# Led_Matrix_Main.net
KiCad netlist of a schematic drawn in Altium Designer
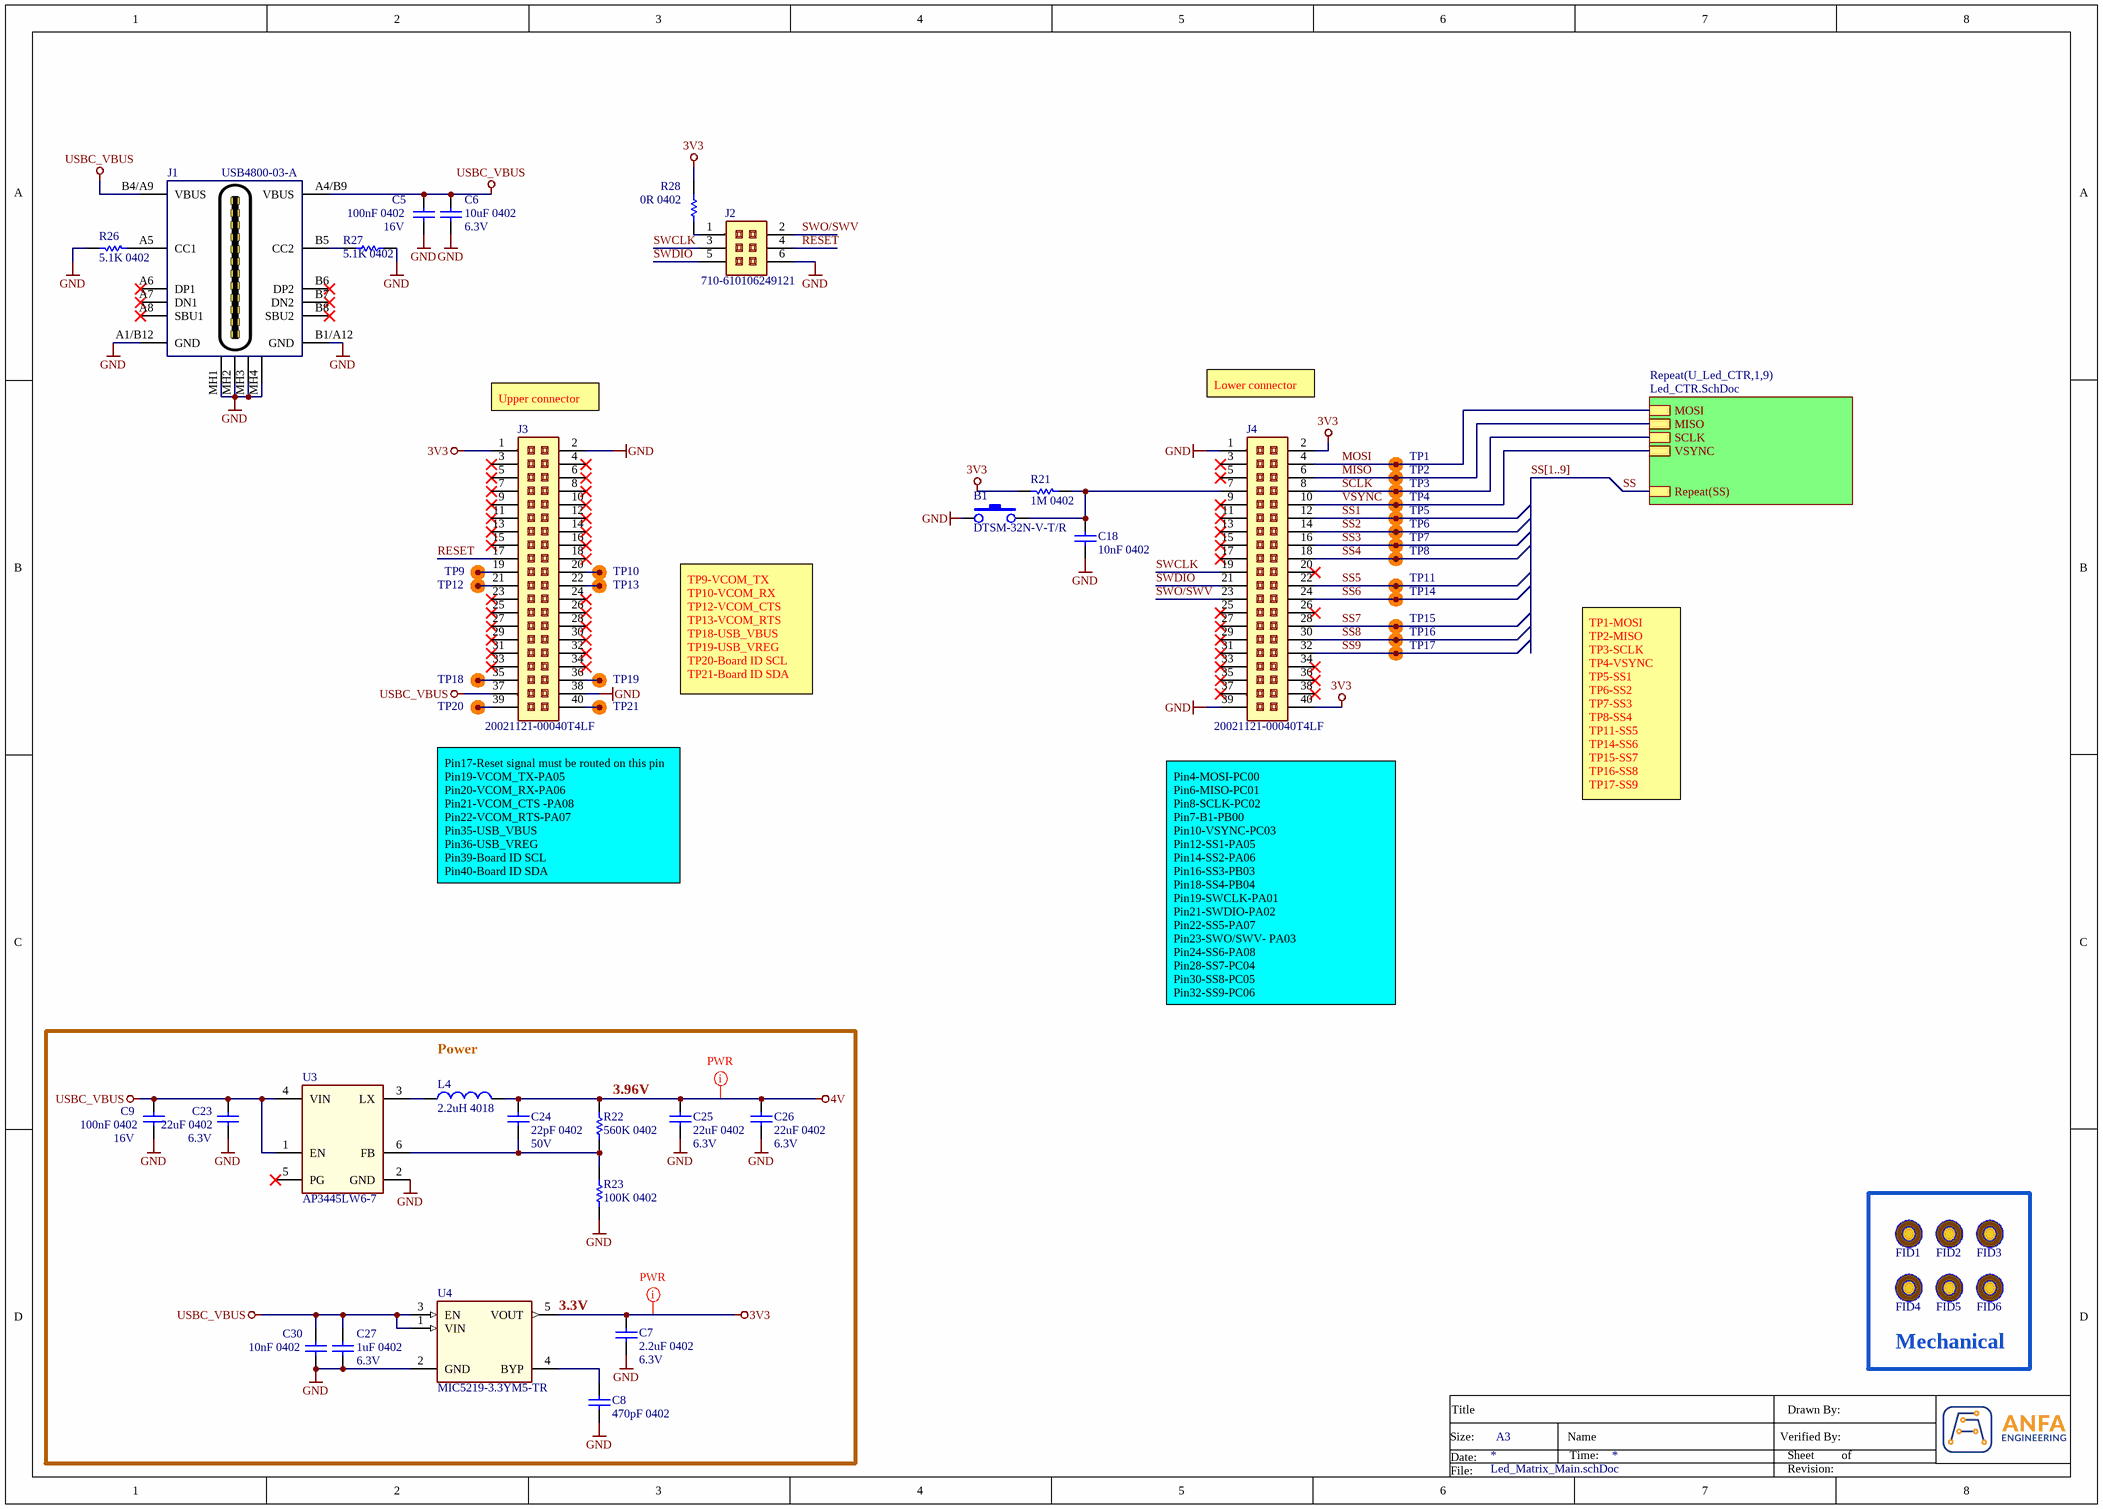
[diagram p0: Led_Matrix_Main.schDoc]

(export (version "E")
  (design (tool "Eeschema 10.0.6"))
  (components
    (comp (ref "B1")
      (value "DTSM-32N-V-T/R")
      (footprint "DTSM-32N-V")
      (description "SWITCH TACTILE SMT 3.5mm * 6mm , brown 160gf")
      (fields (field (name "MANUFACTURER") "Diptronics"))
      (libsource (lib "Led_Matrix") (part "SW-TACTILE_ON/OFF_DTSM-32N-V-T/R"))
    )
    (comp (ref "C5")
      (value "100nF 0402")
      (footprint "CAPC0402(1005)70")
      (description "Surface Mount Ceramic Multilayer Capacitor 100nF, ± 10%, X7R, 16V, 0402")
      (fields
        (field (name "TOLERANCE") "10%")
        (field (name "MANUFACTURER") "Murata")
        (field (name "VOLTAGE") "16V")
      )
      (libsource (lib "Led_Matrix") (part "C_100nF_0402_16V_X7R"))
    )
    (comp (ref "C6")
      (value "10uF 0402")
      (footprint "CAPC0402(1005)70")
      (description "Surface Mount Ceramic Multilayer Capacitor 10uF, ± 20 %, X5R, 6.3V, 0402")
      (fields
        (field (name "TOLERANCE") "20%")
        (field (name "MANUFACTURER") "Murata")
        (field (name "VOLTAGE") "6.3V")
      )
      (libsource (lib "Led_Matrix") (part "C_10uF_0402_6.3V_X5R"))
    )
    (comp (ref "C7")
      (value "2.2uF 0402")
      (footprint "CAPC0402(1005)70")
      (description "Surface Mount Ceramic Multilayer Capacitor 2.2uF, ± 10%, X5R, 6.3V, 0402")
      (fields
        (field (name "MANUFACTURER") "Murata")
        (field (name "MANUFACTURER PART NUMBER") "GRM155R60J225KE01D")
        (field (name "VOLTAGE") "6.3V")
      )
      (libsource (lib "Led_Matrix") (part "C_2.2uF_0402_6.3V_X5R"))
    )
    (comp (ref "C8")
      (value "470pF 0402")
      (footprint "CAPC0402(1005)33")
      (description "Multilayer Ceramic Capacitors MLCC - SMD/SMT 0402 470pF 10V C0G 10%")
      (fields
        (field (name "MANUFACTURER") "Vishay")
        (field (name "MANUFACTURER PART NUMBER") "VJ0402A471KXQPW1BC")
      )
      (libsource (lib "Led_Matrix") (part "C_470pF_0402_10V_C0G"))
    )
    (comp (ref "C9")
      (value "100nF 0402")
      (footprint "CAPC0402(1005)70")
      (description "Surface Mount Ceramic Multilayer Capacitor 100nF, ± 10%, X7R, 16V, 0402")
      (fields
        (field (name "TOLERANCE") "10%")
        (field (name "MANUFACTURER") "Murata")
        (field (name "VOLTAGE") "16V")
      )
      (libsource (lib "Led_Matrix") (part "C_100nF_0402_16V_X7R"))
    )
    (comp (ref "C18")
      (value "10nF 0402")
      (footprint "CAPC0402(1005)33")
      (description "Cap Ceramic 0.01uF 50V X7R 10% SMD 0402 125C Paper T/R")
      (fields (field (name "TOLERANCE") "10%") (field (name "MANUFACTURER") "Vishay Vitramon"))
      (libsource (lib "Led_Matrix") (part "C_10nF_0402_50V_X7R"))
    )
    (comp (ref "C23")
      (value "22uF 0402")
      (footprint "CAPC0402(1005)70")
      (description "Multilayer Ceramic Capacitors MLCC - SMD/SMT 6.3V 22uF X5R 0402 20%")
      (fields
        (field (name "MANUFACTURER") "KYOCERA AVX")
        (field (name "MANUFACTURER PART NUMBER") "04026D226MAT2A")
        (field (name "VOLTAGE") "6.3V")
      )
      (libsource (lib "Led_Matrix") (part "C_22uF_0402_6.3V_X5R"))
    )
    (comp (ref "C24")
      (value "22pF 0402")
      (footprint "CAPC0402(1005)70")
      (description "Surface Mount Ceramic Multilayer Capacitor 22pF, ± 5%, C0G, 50V, 0402")
      (fields
        (field (name "MANUFACTURER") "Kyocera AVX")
        (field (name "MANUFACTURER PART NUMBER") "04025A220JAT2A")
        (field (name "VOLTAGE") "50V")
      )
      (libsource (lib "Led_Matrix") (part "C_22pF_0402_50V_C0G"))
    )
    (comp (ref "C25")
      (value "22uF 0402")
      (footprint "CAPC0402(1005)70")
      (description "Multilayer Ceramic Capacitors MLCC - SMD/SMT 6.3V 22uF X5R 0402 20%")
      (fields
        (field (name "MANUFACTURER") "KYOCERA AVX")
        (field (name "MANUFACTURER PART NUMBER") "04026D226MAT2A")
        (field (name "VOLTAGE") "6.3V")
      )
      (libsource (lib "Led_Matrix") (part "C_22uF_0402_6.3V_X5R"))
    )
    (comp (ref "C26")
      (value "22uF 0402")
      (footprint "CAPC0402(1005)70")
      (description "Multilayer Ceramic Capacitors MLCC - SMD/SMT 6.3V 22uF X5R 0402 20%")
      (fields
        (field (name "MANUFACTURER") "KYOCERA AVX")
        (field (name "MANUFACTURER PART NUMBER") "04026D226MAT2A")
        (field (name "VOLTAGE") "6.3V")
      )
      (libsource (lib "Led_Matrix") (part "C_22uF_0402_6.3V_X5R"))
    )
    (comp (ref "C27")
      (value "1uF 0402")
      (footprint "CAPC0402(1005)70")
      (description "Surface Mount Ceramic Multilayer Capacitor 1uF, ± 20%, X5R, 6.3V, 0402")
      (fields
        (field (name "TOLERANCE") "20%")
        (field (name "MANUFACTURER") "Murata")
        (field (name "VOLTAGE") "6.3V")
      )
      (libsource (lib "Led_Matrix") (part "C_1uF_0402_6.3V_X5R"))
    )
    (comp (ref "C30")
      (value "10nF 0402")
      (footprint "CAPC0402(1005)33")
      (description "Cap Ceramic 0.01uF 50V X7R 10% SMD 0402 125C Paper T/R")
      (fields
        (field (name "MANUFACTURER") "Vishay Vitramon")
        (field (name "MANUFACTURER PART NUMBER") "VJ0402Y103KXACW1BC")
      )
      (libsource (lib "Led_Matrix") (part "C_10nF_0402_50V_X7R"))
    )
    (comp (ref "FID1")
      (value "~")
      (footprint "FID1")
      (description "Fiducial with various available footprints")
      (libsource (lib "AL_Connectors") (part "MECH_FIDUCIAL"))
    )
    (comp (ref "FID2")
      (value "~")
      (footprint "FID1")
      (description "Fiducial with various available footprints")
      (libsource (lib "AL_Connectors") (part "MECH_FIDUCIAL"))
    )
    (comp (ref "FID3")
      (value "~")
      (footprint "FID1")
      (description "Fiducial with various available footprints")
      (libsource (lib "AL_Connectors") (part "MECH_FIDUCIAL"))
    )
    (comp (ref "FID4")
      (value "~")
      (footprint "FID1")
      (description "Fiducial with various available footprints")
      (libsource (lib "AL_Connectors") (part "MECH_FIDUCIAL"))
    )
    (comp (ref "FID5")
      (value "~")
      (footprint "FID1")
      (description "Fiducial with various available footprints")
      (libsource (lib "AL_Connectors") (part "MECH_FIDUCIAL"))
    )
    (comp (ref "FID6")
      (value "~")
      (footprint "FID1")
      (description "Fiducial with various available footprints")
      (libsource (lib "AL_Connectors") (part "MECH_FIDUCIAL"))
    )
    (comp (ref "J1")
      (value "USB4800-03-A")
      (footprint "USB4800-03-A")
      (description "USB Connectors USB2.0 Type C Rcpt, SMT, Hrz, 3.5mm elevated, 16 Pin")
      (fields (field (name "MANUFACTURER") "GCT"))
      (libsource (lib "Led_Matrix") (part "USB-C_3.0_USB4800-03-A"))
    )
    (comp (ref "J2")
      (value "710-610106249121")
      (footprint "HDR_2X3_2.54mm_MALE")
      (description "Headers & Wire Housings WR-PHD 2.54mm Hdr 6P Dual RA Gold")
      (fields
        (field (name "MANUFACTURER") "Wurth Elektronik")
        (field (name "MANUFACTURER PART NUMBER") "610106249121")
      )
      (libsource (lib "Led_Matrix") (part "HEADER_2X3_RA_MALE_2.54mm_710-610106249121"))
    )
    (comp (ref "J3")
      (value "20021121-00040T4LF")
      (footprint "20021121-00040T4LF")
      (description "Headers & Wire Housings 1.27mm BTB, Hdr, SMT Unshrd, 40 P, Tub")
      (fields (field (name "MANUFACTURER") "Amphenol FCI"))
      (libsource (lib "Led_Matrix") (part "HEADER_2X20_RA_MALE_1,27mm_649-221121-00040T4LF"))
    )
    (comp (ref "J4")
      (value "20021121-00040T4LF")
      (footprint "20021121-00040T4LF")
      (description "Headers & Wire Housings 1.27mm BTB, Hdr, SMT Unshrd, 40 P, Tub")
      (fields (field (name "MANUFACTURER") "Amphenol FCI"))
      (libsource (lib "Led_Matrix") (part "HEADER_2X20_RA_MALE_1,27mm_649-221121-00040T4LF"))
    )
    (comp (ref "L4")
      (value "2.2uH 4018")
      (footprint "SMD4018")
      (description "Inductor Power Shielded Wirewound, 2.2uH, 20%, Saturation Current 3.11A, 50.4 mOhms DCR, SMD4018")
      (fields (field (name "TOLERANCE") "20%") (field (name "MANUFACTURER") "Taiyo Yuden"))
      (libsource (lib "Led_Matrix") (part "L_2.2uH_3.11A"))
    )
    (comp (ref "R21")
      (value "1M 0402")
      (footprint "RESC0402(1005)")
      (description "Resistor: thick film; SMD; 0402; 1MΩ; 63mW; ±5%; -55÷155°C")
      (fields
        (field (name "MANUFACTURER") "ROYAL OHM")
        (field (name "MANUFACTURER PART NUMBER") "0402WGJ0105TCE")
      )
      (libsource (lib "Led_Matrix") (part "R_1M_0402_5%"))
    )
    (comp (ref "R22")
      (value "560K 0402")
      (footprint "RESC0402(1005)")
      (description "Rezistor: thick film; SMD; 0402; 560kΩ; 63mW; ±1%; -55÷155°C")
      (fields
        (field (name "MANUFACTURER") "ROYAL OHM")
        (field (name "MANUFACTURER PART NUMBER") "0402WGJ0564TCE")
      )
      (libsource (lib "Led_Matrix") (part "R_560K_0402_1%"))
    )
    (comp (ref "R23")
      (value "100K 0402")
      (footprint "RESC0402(1005)")
      (description "Resistor: thick film; SMD; 0402; 100KΩ; 63mW; ±1%; -55÷155°C")
      (fields (field (name "TOLERANCE") "1%") (field (name "MANUFACTURER") "Yageo"))
      (libsource (lib "Led_Matrix") (part "R_100K_0402_1%"))
    )
    (comp (ref "R26")
      (value "5.1K 0402")
      (footprint "RESC0402(1005)")
      (description "Resistor: thick film; SMD; 0402; 5.1KΩ; 63mW; ±1%; -55÷155°C")
      (fields (field (name "TOLERANCE") "1%") (field (name "MANUFACTURER") "Vishay"))
      (libsource (lib "Led_Matrix") (part "R_5.1K_0402_1%"))
    )
    (comp (ref "R27")
      (value "5.1K 0402")
      (footprint "RESC0402(1005)")
      (description "Resistor: thick film; SMD; 0402; 5.1KΩ; 63mW; ±1%; -55÷155°C")
      (fields (field (name "TOLERANCE") "1%") (field (name "MANUFACTURER") "Vishay"))
      (libsource (lib "Led_Matrix") (part "R_5.1K_0402_1%"))
    )
    (comp (ref "R28")
      (value "0R 0402")
      (footprint "RESC0402(1005)")
      (description "Resistor: thick film; SMD; 0402; 0R; 63mW; ±5%; -55÷155°C")
      (fields
        (field (name "MANUFACTURER") "Royal Electronic Factory")
        (field (name "MANUFACTURER PART NUMBER") "0402WGJ0000TCE")
      )
      (libsource (lib "Led_Matrix") (part "R_0R_0402_5%"))
    )
    (comp (ref "TP1")
      (value "~")
      (footprint "TP_SMD")
      (description "Test Point 1mm")
      (libsource (lib "Led_Matrix") (part "TP_1mm_OLD"))
    )
    (comp (ref "TP2")
      (value "~")
      (footprint "TP_SMD")
      (description "Test Point 1mm")
      (libsource (lib "Led_Matrix") (part "TP_1mm_OLD"))
    )
    (comp (ref "TP3")
      (value "~")
      (footprint "TP_SMD")
      (description "Test Point 1mm")
      (libsource (lib "Led_Matrix") (part "TP_1mm_OLD"))
    )
    (comp (ref "TP4")
      (value "~")
      (footprint "TP_SMD")
      (description "Test Point 1mm")
      (libsource (lib "Led_Matrix") (part "TP_1mm_OLD"))
    )
    (comp (ref "TP5")
      (value "~")
      (footprint "TP_SMD")
      (description "Test Point 1mm")
      (libsource (lib "Led_Matrix") (part "TP_1mm_OLD"))
    )
    (comp (ref "TP6")
      (value "~")
      (footprint "TP_SMD")
      (description "Test Point 1mm")
      (libsource (lib "Led_Matrix") (part "TP_1mm_OLD"))
    )
    (comp (ref "TP7")
      (value "~")
      (footprint "TP_SMD")
      (description "Test Point 1mm")
      (libsource (lib "Led_Matrix") (part "TP_1mm_OLD"))
    )
    (comp (ref "TP8")
      (value "~")
      (footprint "TP_SMD")
      (description "Test Point 1mm")
      (libsource (lib "Led_Matrix") (part "TP_1mm_OLD"))
    )
    (comp (ref "TP9")
      (value "~")
      (footprint "TP_SMD")
      (description "Test Point 1mm")
      (libsource (lib "Led_Matrix") (part "TP_1mm_OLD"))
    )
    (comp (ref "TP10")
      (value "~")
      (footprint "TP_SMD")
      (description "Test Point 1mm")
      (libsource (lib "Led_Matrix") (part "TP_1mm_OLD"))
    )
    (comp (ref "TP11")
      (value "~")
      (footprint "TP_SMD")
      (description "Test Point 1mm")
      (libsource (lib "Led_Matrix") (part "TP_1mm_OLD"))
    )
    (comp (ref "TP12")
      (value "~")
      (footprint "TP_SMD")
      (description "Test Point 1mm")
      (libsource (lib "Led_Matrix") (part "TP_1mm_OLD"))
    )
    (comp (ref "TP13")
      (value "~")
      (footprint "TP_SMD")
      (description "Test Point 1mm")
      (libsource (lib "Led_Matrix") (part "TP_1mm_OLD"))
    )
    (comp (ref "TP14")
      (value "~")
      (footprint "TP_SMD")
      (description "Test Point 1mm")
      (libsource (lib "Led_Matrix") (part "TP_1mm_OLD"))
    )
    (comp (ref "TP15")
      (value "~")
      (footprint "TP_SMD")
      (description "Test Point 1mm")
      (libsource (lib "Led_Matrix") (part "TP_1mm_OLD"))
    )
    (comp (ref "TP16")
      (value "~")
      (footprint "TP_SMD")
      (description "Test Point 1mm")
      (libsource (lib "Led_Matrix") (part "TP_1mm_OLD"))
    )
    (comp (ref "TP17")
      (value "~")
      (footprint "TP_SMD")
      (description "Test Point 1mm")
      (libsource (lib "Led_Matrix") (part "TP_1mm_OLD"))
    )
    (comp (ref "TP18")
      (value "~")
      (footprint "TP_SMD")
      (description "Test Point 1mm")
      (libsource (lib "Led_Matrix") (part "TP_1mm_OLD"))
    )
    (comp (ref "TP19")
      (value "~")
      (footprint "TP_SMD")
      (description "Test Point 1mm")
      (libsource (lib "Led_Matrix") (part "TP_1mm_OLD"))
    )
    (comp (ref "TP20")
      (value "~")
      (footprint "TP_SMD")
      (description "Test Point 1mm")
      (libsource (lib "Led_Matrix") (part "TP_1mm_OLD"))
    )
    (comp (ref "TP21")
      (value "~")
      (footprint "TP_SMD")
      (description "Test Point 1mm")
      (libsource (lib "Led_Matrix") (part "TP_1mm_OLD"))
    )
    (comp (ref "U3")
      (value "AP3445LW6-7")
      (footprint "SOT23-6")
      (description "Buck Switching Regulator IC Positive Adjustable 0.6V 1 Output 2A SOT-23-6")
      (fields (field (name "MANUFACTURER") "Diodes Incorporated"))
      (libsource (lib "Led_Matrix") (part "VR_BUCK_AP3445LW6-7"))
    )
    (comp (ref "U4")
      (value "MIC5219-3.3YM5-TR")
      (footprint "SOT23-5")
      (description "LDO Voltage Regulators, Adjustable Output Voltage, Output Current 500mA, SOT-23-5")
      (fields (field (name "MANUFACTURER") "Microchip Technology"))
      (libsource (lib "Led_Matrix") (part "VR_LDO_MIC5219-3.3YM5-TR"))
    )
  )
  (nets
    (net (code "1") (name "/MISO") (class "Default")
      (node (ref "J4") (pin "6") (pinfunction "6_6") (pintype "passive"))
      (node (ref "TP2") (pin "1") (pinfunction "1_1") (pintype "passive"))
    )
    (net (code "2") (name "/MOSI") (class "Default")
      (node (ref "J4") (pin "4") (pinfunction "4_4") (pintype "passive"))
      (node (ref "TP1") (pin "1") (pinfunction "1_1") (pintype "passive"))
    )
    (net (code "3") (name "/RESET") (class "Default")
      (node (ref "J2") (pin "4") (pinfunction "4_4") (pintype "passive"))
      (node (ref "J3") (pin "17") (pinfunction "17_17") (pintype "passive"))
    )
    (net (code "4") (name "/SCLK") (class "Default")
      (node (ref "J4") (pin "8") (pinfunction "8_8") (pintype "passive"))
      (node (ref "TP3") (pin "1") (pinfunction "1_1") (pintype "passive"))
    )
    (net (code "6") (name "/SS1") (class "Default")
      (node (ref "J4") (pin "12") (pinfunction "12_12") (pintype "passive"))
      (node (ref "TP5") (pin "1") (pinfunction "1_1") (pintype "passive"))
    )
    (net (code "7") (name "/SS2") (class "Default")
      (node (ref "J4") (pin "14") (pinfunction "14_14") (pintype "passive"))
      (node (ref "TP6") (pin "1") (pinfunction "1_1") (pintype "passive"))
    )
    (net (code "8") (name "/SS3") (class "Default")
      (node (ref "J4") (pin "16") (pinfunction "16_16") (pintype "passive"))
      (node (ref "TP7") (pin "1") (pinfunction "1_1") (pintype "passive"))
    )
    (net (code "9") (name "/SS4") (class "Default")
      (node (ref "J4") (pin "18") (pinfunction "18_18") (pintype "passive"))
      (node (ref "TP8") (pin "1") (pinfunction "1_1") (pintype "passive"))
    )
    (net (code "10") (name "/SS5") (class "Default")
      (node (ref "J4") (pin "22") (pinfunction "22_22") (pintype "passive"))
      (node (ref "TP11") (pin "1") (pinfunction "1_1") (pintype "passive"))
    )
    (net (code "11") (name "/SS6") (class "Default")
      (node (ref "J4") (pin "24") (pinfunction "24_24") (pintype "passive"))
      (node (ref "TP14") (pin "1") (pinfunction "1_1") (pintype "passive"))
    )
    (net (code "12") (name "/SS7") (class "Default")
      (node (ref "J4") (pin "28") (pinfunction "28_28") (pintype "passive"))
      (node (ref "TP15") (pin "1") (pinfunction "1_1") (pintype "passive"))
    )
    (net (code "13") (name "/SS8") (class "Default")
      (node (ref "J4") (pin "30") (pinfunction "30_30") (pintype "passive"))
      (node (ref "TP16") (pin "1") (pinfunction "1_1") (pintype "passive"))
    )
    (net (code "14") (name "/SS9") (class "Default")
      (node (ref "J4") (pin "32") (pinfunction "32_32") (pintype "passive"))
      (node (ref "TP17") (pin "1") (pinfunction "1_1") (pintype "passive"))
    )
    (net (code "16") (name "/SWCLK") (class "Default")
      (node (ref "J2") (pin "3") (pinfunction "3_3") (pintype "passive"))
      (node (ref "J4") (pin "19") (pinfunction "19_19") (pintype "passive"))
    )
    (net (code "17") (name "/SWDIO") (class "Default")
      (node (ref "J2") (pin "5") (pinfunction "5_5") (pintype "passive"))
      (node (ref "J4") (pin "21") (pinfunction "21_21") (pintype "passive"))
    )
    (net (code "18") (name "/SWO{slash}SWV") (class "Default")
      (node (ref "J2") (pin "2") (pinfunction "2_2") (pintype "passive"))
      (node (ref "J4") (pin "23") (pinfunction "23_23") (pintype "passive"))
    )
    (net (code "19") (name "/VSYNC") (class "Default")
      (node (ref "J4") (pin "10") (pinfunction "10_10") (pintype "passive"))
      (node (ref "TP4") (pin "1") (pinfunction "1_1") (pintype "passive"))
    )
    (net (code "20") (name "3V3") (class "Default")
      (node (ref "C7") (pin "2") (pinfunction "2_2") (pintype "passive"))
      (node (ref "J3") (pin "1") (pinfunction "1_1") (pintype "passive"))
      (node (ref "J4") (pin "2") (pinfunction "2_2") (pintype "passive"))
      (node (ref "J4") (pin "40") (pinfunction "40_40") (pintype "passive"))
      (node (ref "R21") (pin "1") (pinfunction "1_1") (pintype "passive"))
      (node (ref "R28") (pin "2") (pinfunction "2_2") (pintype "passive"))
      (node (ref "U4") (pin "5") (pinfunction "VOUT_5") (pintype "output"))
    )
    (net (code "21") (name "4V") (class "Default")
      (node (ref "C24") (pin "2") (pinfunction "2_2") (pintype "passive"))
      (node (ref "C25") (pin "1") (pinfunction "1_1") (pintype "passive"))
      (node (ref "C26") (pin "1") (pinfunction "1_1") (pintype "passive"))
      (node (ref "L4") (pin "2") (pinfunction "2_2") (pintype "passive"))
      (node (ref "R22") (pin "2") (pinfunction "2_2") (pintype "passive"))
    )
    (net (code "22") (name "GND") (class "Default")
      (node (ref "B1") (pin "2") (pinfunction "2_2") (pintype "passive"))
      (node (ref "C18") (pin "1") (pinfunction "1_1") (pintype "passive"))
      (node (ref "C23") (pin "1") (pinfunction "1_1") (pintype "passive"))
      (node (ref "C25") (pin "2") (pinfunction "2_2") (pintype "passive"))
      (node (ref "C26") (pin "2") (pinfunction "2_2") (pintype "passive"))
      (node (ref "C27") (pin "1") (pinfunction "1_1") (pintype "passive"))
      (node (ref "C30") (pin "1") (pinfunction "1_1") (pintype "passive"))
      (node (ref "C5") (pin "1") (pinfunction "1_1") (pintype "passive"))
      (node (ref "C6") (pin "1") (pinfunction "1_1") (pintype "passive"))
      (node (ref "C7") (pin "1") (pinfunction "1_1") (pintype "passive"))
      (node (ref "C8") (pin "1") (pinfunction "1_1") (pintype "passive"))
      (node (ref "C9") (pin "1") (pinfunction "1_1") (pintype "passive"))
      (node (ref "J1") (pin "A1/B12") (pinfunction "GND_A1/B12") (pintype "passive"))
      (node (ref "J1") (pin "B1/A12") (pinfunction "GND_B1/A12") (pintype "passive"))
      (node (ref "J1") (pin "MH1") (pinfunction "MH1_MH1") (pintype "passive"))
      (node (ref "J1") (pin "MH2") (pinfunction "MH2_MH2") (pintype "passive"))
      (node (ref "J1") (pin "MH3") (pinfunction "MH3_MH3") (pintype "passive"))
      (node (ref "J1") (pin "MH4") (pinfunction "MH4_MH4") (pintype "passive"))
      (node (ref "J2") (pin "6") (pinfunction "6_6") (pintype "passive"))
      (node (ref "J3") (pin "2") (pinfunction "2_2") (pintype "passive"))
      (node (ref "J3") (pin "38") (pinfunction "38_38") (pintype "passive"))
      (node (ref "J4") (pin "1") (pinfunction "1_1") (pintype "passive"))
      (node (ref "J4") (pin "39") (pinfunction "39_39") (pintype "passive"))
      (node (ref "R23") (pin "1") (pinfunction "1_1") (pintype "passive"))
      (node (ref "R26") (pin "2") (pinfunction "2_2") (pintype "passive"))
      (node (ref "R27") (pin "2") (pinfunction "2_2") (pintype "passive"))
      (node (ref "U3") (pin "2") (pinfunction "GND_2") (pintype "passive"))
      (node (ref "U4") (pin "2") (pinfunction "GND_2") (pintype "passive"))
    )
    (net (code "23") (name "Net-(B1-Pad1)") (class "Default")
      (node (ref "B1") (pin "1") (pinfunction "1_1") (pintype "passive"))
      (node (ref "C18") (pin "2") (pinfunction "2_2") (pintype "passive"))
      (node (ref "J4") (pin "7") (pinfunction "7_7") (pintype "passive"))
      (node (ref "R21") (pin "2") (pinfunction "2_2") (pintype "passive"))
    )
    (net (code "24") (name "Net-(J1-CC1)") (class "Default")
      (node (ref "J1") (pin "A5") (pinfunction "CC1_A5") (pintype "passive"))
      (node (ref "R26") (pin "1") (pinfunction "1_1") (pintype "passive"))
    )
    (net (code "25") (name "Net-(J1-CC2)") (class "Default")
      (node (ref "J1") (pin "B5") (pinfunction "CC2_B5") (pintype "passive"))
      (node (ref "R27") (pin "1") (pinfunction "1_1") (pintype "passive"))
    )
    (net (code "26") (name "Net-(J2-Pad1)") (class "Default")
      (node (ref "J2") (pin "1") (pinfunction "1_1") (pintype "passive"))
      (node (ref "R28") (pin "1") (pinfunction "1_1") (pintype "passive"))
    )
    (net (code "27") (name "Net-(J3-Pad19)") (class "Default")
      (node (ref "J3") (pin "19") (pinfunction "19_19") (pintype "passive"))
      (node (ref "TP9") (pin "1") (pinfunction "1_1") (pintype "passive"))
    )
    (net (code "28") (name "Net-(J3-Pad20)") (class "Default")
      (node (ref "J3") (pin "20") (pinfunction "20_20") (pintype "passive"))
      (node (ref "TP10") (pin "1") (pinfunction "1_1") (pintype "passive"))
    )
    (net (code "29") (name "Net-(J3-Pad21)") (class "Default")
      (node (ref "J3") (pin "21") (pinfunction "21_21") (pintype "passive"))
      (node (ref "TP12") (pin "1") (pinfunction "1_1") (pintype "passive"))
    )
    (net (code "30") (name "Net-(J3-Pad22)") (class "Default")
      (node (ref "J3") (pin "22") (pinfunction "22_22") (pintype "passive"))
      (node (ref "TP13") (pin "1") (pinfunction "1_1") (pintype "passive"))
    )
    (net (code "31") (name "Net-(J3-Pad35)") (class "Default")
      (node (ref "J3") (pin "35") (pinfunction "35_35") (pintype "passive"))
      (node (ref "TP18") (pin "1") (pinfunction "1_1") (pintype "passive"))
    )
    (net (code "32") (name "Net-(J3-Pad36)") (class "Default")
      (node (ref "J3") (pin "36") (pinfunction "36_36") (pintype "passive"))
      (node (ref "TP19") (pin "1") (pinfunction "1_1") (pintype "passive"))
    )
    (net (code "33") (name "Net-(J3-Pad39)") (class "Default")
      (node (ref "J3") (pin "39") (pinfunction "39_39") (pintype "passive"))
      (node (ref "TP20") (pin "1") (pinfunction "1_1") (pintype "passive"))
    )
    (net (code "34") (name "Net-(J3-Pad40)") (class "Default")
      (node (ref "J3") (pin "40") (pinfunction "40_40") (pintype "passive"))
      (node (ref "TP21") (pin "1") (pinfunction "1_1") (pintype "passive"))
    )
    (net (code "35") (name "Net-(U3-FB)") (class "Default")
      (node (ref "C24") (pin "1") (pinfunction "1_1") (pintype "passive"))
      (node (ref "R22") (pin "1") (pinfunction "1_1") (pintype "passive"))
      (node (ref "R23") (pin "2") (pinfunction "2_2") (pintype "passive"))
      (node (ref "U3") (pin "6") (pinfunction "FB_6") (pintype "passive"))
    )
    (net (code "36") (name "Net-(U3-LX)") (class "Default")
      (node (ref "L4") (pin "1") (pinfunction "1_1") (pintype "passive"))
      (node (ref "U3") (pin "3") (pinfunction "LX_3") (pintype "passive"))
    )
    (net (code "37") (name "Net-(U4-BYP)") (class "Default")
      (node (ref "C8") (pin "2") (pinfunction "2_2") (pintype "passive"))
      (node (ref "U4") (pin "4") (pinfunction "BYP_4") (pintype "passive"))
    )
    (net (code "38") (name "USBC_VBUS") (class "Default")
      (node (ref "C23") (pin "2") (pinfunction "2_2") (pintype "passive"))
      (node (ref "C27") (pin "2") (pinfunction "2_2") (pintype "passive"))
      (node (ref "C30") (pin "2") (pinfunction "2_2") (pintype "passive"))
      (node (ref "C5") (pin "2") (pinfunction "2_2") (pintype "passive"))
      (node (ref "C6") (pin "2") (pinfunction "2_2") (pintype "passive"))
      (node (ref "C9") (pin "2") (pinfunction "2_2") (pintype "passive"))
      (node (ref "J1") (pin "A4/B9") (pinfunction "VBUS_A4/B9") (pintype "power_in"))
      (node (ref "J1") (pin "B4/A9") (pinfunction "VBUS_B4/A9") (pintype "power_in"))
      (node (ref "J3") (pin "37") (pinfunction "37_37") (pintype "passive"))
      (node (ref "U3") (pin "1") (pinfunction "EN_1") (pintype "passive"))
      (node (ref "U3") (pin "4") (pinfunction "VIN_4") (pintype "passive"))
      (node (ref "U4") (pin "1") (pinfunction "VIN_1") (pintype "input"))
      (node (ref "U4") (pin "3") (pinfunction "EN_3") (pintype "input"))
    )
    (net (code "39") (name "unconnected-(J1-DN1-PadA7)") (class "Default")
      (node (ref "J1") (pin "A7") (pinfunction "DN1_A7") (pintype "passive+no_connect"))
    )
    (net (code "40") (name "unconnected-(J1-DN2-PadB7)") (class "Default")
      (node (ref "J1") (pin "B7") (pinfunction "DN2_B7") (pintype "passive+no_connect"))
    )
    (net (code "41") (name "unconnected-(J1-DP1-PadA6)") (class "Default")
      (node (ref "J1") (pin "A6") (pinfunction "DP1_A6") (pintype "passive+no_connect"))
    )
    (net (code "42") (name "unconnected-(J1-DP2-PadB6)") (class "Default")
      (node (ref "J1") (pin "B6") (pinfunction "DP2_B6") (pintype "passive+no_connect"))
    )
    (net (code "43") (name "unconnected-(J1-SBU1-PadA8)") (class "Default")
      (node (ref "J1") (pin "A8") (pinfunction "SBU1_A8") (pintype "passive+no_connect"))
    )
    (net (code "44") (name "unconnected-(J1-SBU2-PadB8)") (class "Default")
      (node (ref "J1") (pin "B8") (pinfunction "SBU2_B8") (pintype "passive+no_connect"))
    )
    (net (code "45") (name "unconnected-(J3-Pad3)") (class "Default")
      (node (ref "J3") (pin "3") (pinfunction "3_3") (pintype "passive+no_connect"))
    )
    (net (code "46") (name "unconnected-(J3-Pad4)") (class "Default")
      (node (ref "J3") (pin "4") (pinfunction "4_4") (pintype "passive+no_connect"))
    )
    (net (code "47") (name "unconnected-(J3-Pad5)") (class "Default")
      (node (ref "J3") (pin "5") (pinfunction "5_5") (pintype "passive+no_connect"))
    )
    (net (code "48") (name "unconnected-(J3-Pad6)") (class "Default")
      (node (ref "J3") (pin "6") (pinfunction "6_6") (pintype "passive+no_connect"))
    )
    (net (code "49") (name "unconnected-(J3-Pad7)") (class "Default")
      (node (ref "J3") (pin "7") (pinfunction "7_7") (pintype "passive+no_connect"))
    )
    (net (code "50") (name "unconnected-(J3-Pad8)") (class "Default")
      (node (ref "J3") (pin "8") (pinfunction "8_8") (pintype "passive+no_connect"))
    )
    (net (code "51") (name "unconnected-(J3-Pad9)") (class "Default")
      (node (ref "J3") (pin "9") (pinfunction "9_9") (pintype "passive+no_connect"))
    )
    (net (code "52") (name "unconnected-(J3-Pad10)") (class "Default")
      (node (ref "J3") (pin "10") (pinfunction "10_10") (pintype "passive+no_connect"))
    )
    (net (code "53") (name "unconnected-(J3-Pad11)") (class "Default")
      (node (ref "J3") (pin "11") (pinfunction "11_11") (pintype "passive+no_connect"))
    )
    (net (code "54") (name "unconnected-(J3-Pad12)") (class "Default")
      (node (ref "J3") (pin "12") (pinfunction "12_12") (pintype "passive+no_connect"))
    )
    (net (code "55") (name "unconnected-(J3-Pad13)") (class "Default")
      (node (ref "J3") (pin "13") (pinfunction "13_13") (pintype "passive+no_connect"))
    )
    (net (code "56") (name "unconnected-(J3-Pad14)") (class "Default")
      (node (ref "J3") (pin "14") (pinfunction "14_14") (pintype "passive+no_connect"))
    )
    (net (code "57") (name "unconnected-(J3-Pad15)") (class "Default")
      (node (ref "J3") (pin "15") (pinfunction "15_15") (pintype "passive+no_connect"))
    )
    (net (code "58") (name "unconnected-(J3-Pad16)") (class "Default")
      (node (ref "J3") (pin "16") (pinfunction "16_16") (pintype "passive+no_connect"))
    )
    (net (code "59") (name "unconnected-(J3-Pad18)") (class "Default")
      (node (ref "J3") (pin "18") (pinfunction "18_18") (pintype "passive+no_connect"))
    )
    (net (code "60") (name "unconnected-(J3-Pad23)") (class "Default")
      (node (ref "J3") (pin "23") (pinfunction "23_23") (pintype "passive+no_connect"))
    )
    (net (code "61") (name "unconnected-(J3-Pad24)") (class "Default")
      (node (ref "J3") (pin "24") (pinfunction "24_24") (pintype "passive+no_connect"))
    )
    (net (code "62") (name "unconnected-(J3-Pad25)") (class "Default")
      (node (ref "J3") (pin "25") (pinfunction "25_25") (pintype "passive+no_connect"))
    )
    (net (code "63") (name "unconnected-(J3-Pad26)") (class "Default")
      (node (ref "J3") (pin "26") (pinfunction "26_26") (pintype "passive+no_connect"))
    )
    (net (code "64") (name "unconnected-(J3-Pad27)") (class "Default")
      (node (ref "J3") (pin "27") (pinfunction "27_27") (pintype "passive+no_connect"))
    )
    (net (code "65") (name "unconnected-(J3-Pad28)") (class "Default")
      (node (ref "J3") (pin "28") (pinfunction "28_28") (pintype "passive+no_connect"))
    )
    (net (code "66") (name "unconnected-(J3-Pad29)") (class "Default")
      (node (ref "J3") (pin "29") (pinfunction "29_29") (pintype "passive+no_connect"))
    )
    (net (code "67") (name "unconnected-(J3-Pad30)") (class "Default")
      (node (ref "J3") (pin "30") (pinfunction "30_30") (pintype "passive+no_connect"))
    )
    (net (code "68") (name "unconnected-(J3-Pad31)") (class "Default")
      (node (ref "J3") (pin "31") (pinfunction "31_31") (pintype "passive+no_connect"))
    )
    (net (code "69") (name "unconnected-(J3-Pad32)") (class "Default")
      (node (ref "J3") (pin "32") (pinfunction "32_32") (pintype "passive+no_connect"))
    )
    (net (code "70") (name "unconnected-(J3-Pad33)") (class "Default")
      (node (ref "J3") (pin "33") (pinfunction "33_33") (pintype "passive+no_connect"))
    )
    (net (code "71") (name "unconnected-(J3-Pad34)") (class "Default")
      (node (ref "J3") (pin "34") (pinfunction "34_34") (pintype "passive+no_connect"))
    )
    (net (code "72") (name "unconnected-(J4-Pad3)") (class "Default")
      (node (ref "J4") (pin "3") (pinfunction "3_3") (pintype "passive+no_connect"))
    )
    (net (code "73") (name "unconnected-(J4-Pad5)") (class "Default")
      (node (ref "J4") (pin "5") (pinfunction "5_5") (pintype "passive+no_connect"))
    )
    (net (code "74") (name "unconnected-(J4-Pad9)") (class "Default")
      (node (ref "J4") (pin "9") (pinfunction "9_9") (pintype "passive+no_connect"))
    )
    (net (code "75") (name "unconnected-(J4-Pad11)") (class "Default")
      (node (ref "J4") (pin "11") (pinfunction "11_11") (pintype "passive+no_connect"))
    )
    (net (code "76") (name "unconnected-(J4-Pad13)") (class "Default")
      (node (ref "J4") (pin "13") (pinfunction "13_13") (pintype "passive+no_connect"))
    )
    (net (code "77") (name "unconnected-(J4-Pad15)") (class "Default")
      (node (ref "J4") (pin "15") (pinfunction "15_15") (pintype "passive+no_connect"))
    )
    (net (code "78") (name "unconnected-(J4-Pad17)") (class "Default")
      (node (ref "J4") (pin "17") (pinfunction "17_17") (pintype "passive+no_connect"))
    )
    (net (code "79") (name "unconnected-(J4-Pad20)") (class "Default")
      (node (ref "J4") (pin "20") (pinfunction "20_20") (pintype "passive+no_connect"))
    )
    (net (code "80") (name "unconnected-(J4-Pad25)") (class "Default")
      (node (ref "J4") (pin "25") (pinfunction "25_25") (pintype "passive+no_connect"))
    )
    (net (code "81") (name "unconnected-(J4-Pad26)") (class "Default")
      (node (ref "J4") (pin "26") (pinfunction "26_26") (pintype "passive+no_connect"))
    )
    (net (code "82") (name "unconnected-(J4-Pad27)") (class "Default")
      (node (ref "J4") (pin "27") (pinfunction "27_27") (pintype "passive+no_connect"))
    )
    (net (code "83") (name "unconnected-(J4-Pad29)") (class "Default")
      (node (ref "J4") (pin "29") (pinfunction "29_29") (pintype "passive+no_connect"))
    )
    (net (code "84") (name "unconnected-(J4-Pad31)") (class "Default")
      (node (ref "J4") (pin "31") (pinfunction "31_31") (pintype "passive+no_connect"))
    )
    (net (code "85") (name "unconnected-(J4-Pad33)") (class "Default")
      (node (ref "J4") (pin "33") (pinfunction "33_33") (pintype "passive+no_connect"))
    )
    (net (code "86") (name "unconnected-(J4-Pad34)") (class "Default")
      (node (ref "J4") (pin "34") (pinfunction "34_34") (pintype "passive+no_connect"))
    )
    (net (code "87") (name "unconnected-(J4-Pad35)") (class "Default")
      (node (ref "J4") (pin "35") (pinfunction "35_35") (pintype "passive+no_connect"))
    )
    (net (code "88") (name "unconnected-(J4-Pad36)") (class "Default")
      (node (ref "J4") (pin "36") (pinfunction "36_36") (pintype "passive+no_connect"))
    )
    (net (code "89") (name "unconnected-(J4-Pad37)") (class "Default")
      (node (ref "J4") (pin "37") (pinfunction "37_37") (pintype "passive+no_connect"))
    )
    (net (code "90") (name "unconnected-(J4-Pad38)") (class "Default")
      (node (ref "J4") (pin "38") (pinfunction "38_38") (pintype "passive+no_connect"))
    )
    (net (code "91") (name "unconnected-(U3-PG-Pad5)") (class "Default")
      (node (ref "U3") (pin "5") (pinfunction "PG_5") (pintype "passive+no_connect"))
    )
  )
)
